# LEDFLX.net
KiCad netlist of a schematic drawn in Altium Designer
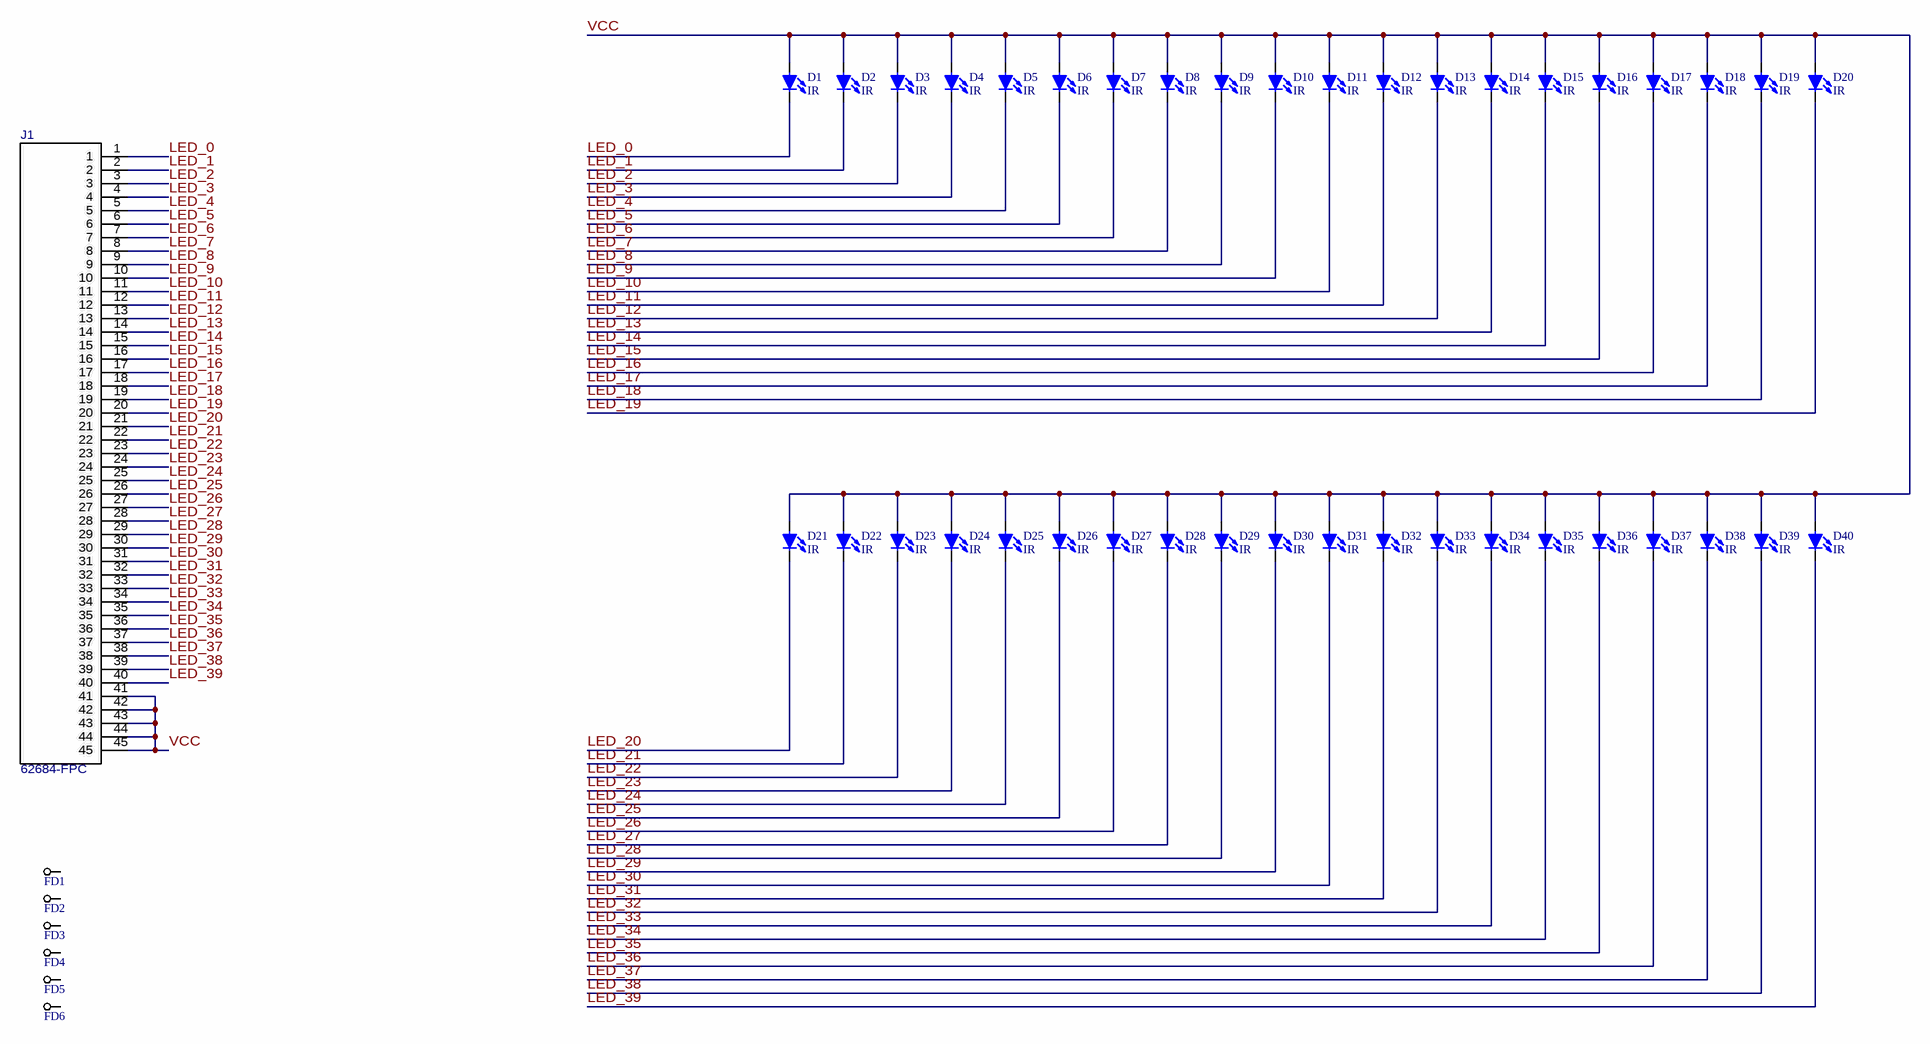
[diagram p0: LEDFLX.SchDoc]

(export (version "E")
  (design (tool "Eeschema 10.0.6"))
  (components
    (comp (ref "D1")
      (value "LED")
      (footprint "VISHAY_PLCC2_A")
      (fields (field (name "MANUFACTURER") "Vishay") (field (name "COLOR") "IR"))
      (libsource (lib "master") (part "LED"))
    )
    (comp (ref "D2")
      (value "LED")
      (footprint "VISHAY_PLCC2_A")
      (fields (field (name "MANUFACTURER") "Vishay") (field (name "COLOR") "IR"))
      (libsource (lib "master") (part "LED"))
    )
    (comp (ref "D3")
      (value "LED")
      (footprint "VISHAY_PLCC2_A")
      (fields (field (name "MANUFACTURER") "Vishay") (field (name "COLOR") "IR"))
      (libsource (lib "master") (part "LED"))
    )
    (comp (ref "D4")
      (value "LED")
      (footprint "VISHAY_PLCC2_A")
      (fields (field (name "MANUFACTURER") "Vishay") (field (name "COLOR") "IR"))
      (libsource (lib "master") (part "LED"))
    )
    (comp (ref "D5")
      (value "LED")
      (footprint "VISHAY_PLCC2_A")
      (fields (field (name "MANUFACTURER") "Vishay") (field (name "COLOR") "IR"))
      (libsource (lib "master") (part "LED"))
    )
    (comp (ref "D6")
      (value "LED")
      (footprint "VISHAY_PLCC2_A")
      (fields (field (name "MANUFACTURER") "Vishay") (field (name "COLOR") "IR"))
      (libsource (lib "master") (part "LED"))
    )
    (comp (ref "D7")
      (value "LED")
      (footprint "VISHAY_PLCC2_A")
      (fields (field (name "MANUFACTURER") "Vishay") (field (name "COLOR") "IR"))
      (libsource (lib "master") (part "LED"))
    )
    (comp (ref "D8")
      (value "LED")
      (footprint "VISHAY_PLCC2_A")
      (fields (field (name "MANUFACTURER") "Vishay") (field (name "COLOR") "IR"))
      (libsource (lib "master") (part "LED"))
    )
    (comp (ref "D9")
      (value "LED")
      (footprint "VISHAY_PLCC2_A")
      (fields (field (name "MANUFACTURER") "Vishay") (field (name "COLOR") "IR"))
      (libsource (lib "master") (part "LED"))
    )
    (comp (ref "D10")
      (value "LED")
      (footprint "VISHAY_PLCC2_A")
      (fields (field (name "MANUFACTURER") "Vishay") (field (name "COLOR") "IR"))
      (libsource (lib "master") (part "LED"))
    )
    (comp (ref "D11")
      (value "LED")
      (footprint "VISHAY_PLCC2_A")
      (fields (field (name "MANUFACTURER") "Vishay") (field (name "COLOR") "IR"))
      (libsource (lib "master") (part "LED"))
    )
    (comp (ref "D12")
      (value "LED")
      (footprint "VISHAY_PLCC2_A")
      (fields (field (name "MANUFACTURER") "Vishay") (field (name "COLOR") "IR"))
      (libsource (lib "master") (part "LED"))
    )
    (comp (ref "D13")
      (value "LED")
      (footprint "VISHAY_PLCC2_A")
      (fields (field (name "MANUFACTURER") "Vishay") (field (name "COLOR") "IR"))
      (libsource (lib "master") (part "LED"))
    )
    (comp (ref "D14")
      (value "LED")
      (footprint "VISHAY_PLCC2_A")
      (fields (field (name "MANUFACTURER") "Vishay") (field (name "COLOR") "IR"))
      (libsource (lib "master") (part "LED"))
    )
    (comp (ref "D15")
      (value "LED")
      (footprint "VISHAY_PLCC2_A")
      (fields (field (name "MANUFACTURER") "Vishay") (field (name "COLOR") "IR"))
      (libsource (lib "master") (part "LED"))
    )
    (comp (ref "D16")
      (value "LED")
      (footprint "VISHAY_PLCC2_A")
      (fields (field (name "MANUFACTURER") "Vishay") (field (name "COLOR") "IR"))
      (libsource (lib "master") (part "LED"))
    )
    (comp (ref "D17")
      (value "LED")
      (footprint "VISHAY_PLCC2_A")
      (fields (field (name "MANUFACTURER") "Vishay") (field (name "COLOR") "IR"))
      (libsource (lib "master") (part "LED"))
    )
    (comp (ref "D18")
      (value "LED")
      (footprint "VISHAY_PLCC2_A")
      (fields (field (name "MANUFACTURER") "Vishay") (field (name "COLOR") "IR"))
      (libsource (lib "master") (part "LED"))
    )
    (comp (ref "D19")
      (value "LED")
      (footprint "VISHAY_PLCC2_A")
      (fields (field (name "MANUFACTURER") "Vishay") (field (name "COLOR") "IR"))
      (libsource (lib "master") (part "LED"))
    )
    (comp (ref "D20")
      (value "LED")
      (footprint "VISHAY_PLCC2_A")
      (fields (field (name "MANUFACTURER") "Vishay") (field (name "COLOR") "IR"))
      (libsource (lib "master") (part "LED"))
    )
    (comp (ref "D21")
      (value "LED")
      (footprint "VISHAY_PLCC2_A")
      (fields (field (name "MANUFACTURER") "Vishay") (field (name "COLOR") "IR"))
      (libsource (lib "master") (part "LED"))
    )
    (comp (ref "D22")
      (value "LED")
      (footprint "VISHAY_PLCC2_A")
      (fields (field (name "MANUFACTURER") "Vishay") (field (name "COLOR") "IR"))
      (libsource (lib "master") (part "LED"))
    )
    (comp (ref "D23")
      (value "LED")
      (footprint "VISHAY_PLCC2_A")
      (fields (field (name "MANUFACTURER") "Vishay") (field (name "COLOR") "IR"))
      (libsource (lib "master") (part "LED"))
    )
    (comp (ref "D24")
      (value "LED")
      (footprint "VISHAY_PLCC2_A")
      (fields (field (name "MANUFACTURER") "Vishay") (field (name "COLOR") "IR"))
      (libsource (lib "master") (part "LED"))
    )
    (comp (ref "D25")
      (value "LED")
      (footprint "VISHAY_PLCC2_A")
      (fields (field (name "MANUFACTURER") "Vishay") (field (name "COLOR") "IR"))
      (libsource (lib "master") (part "LED"))
    )
    (comp (ref "D26")
      (value "LED")
      (footprint "VISHAY_PLCC2_A")
      (fields (field (name "MANUFACTURER") "Vishay") (field (name "COLOR") "IR"))
      (libsource (lib "master") (part "LED"))
    )
    (comp (ref "D27")
      (value "LED")
      (footprint "VISHAY_PLCC2_A")
      (fields (field (name "MANUFACTURER") "Vishay") (field (name "COLOR") "IR"))
      (libsource (lib "master") (part "LED"))
    )
    (comp (ref "D28")
      (value "LED")
      (footprint "VISHAY_PLCC2_A")
      (fields (field (name "MANUFACTURER") "Vishay") (field (name "COLOR") "IR"))
      (libsource (lib "master") (part "LED"))
    )
    (comp (ref "D29")
      (value "LED")
      (footprint "VISHAY_PLCC2_A")
      (fields (field (name "MANUFACTURER") "Vishay") (field (name "COLOR") "IR"))
      (libsource (lib "master") (part "LED"))
    )
    (comp (ref "D30")
      (value "LED")
      (footprint "VISHAY_PLCC2_A")
      (fields (field (name "MANUFACTURER") "Vishay") (field (name "COLOR") "IR"))
      (libsource (lib "master") (part "LED"))
    )
    (comp (ref "D31")
      (value "LED")
      (footprint "VISHAY_PLCC2_A")
      (fields (field (name "MANUFACTURER") "Vishay") (field (name "COLOR") "IR"))
      (libsource (lib "master") (part "LED"))
    )
    (comp (ref "D32")
      (value "LED")
      (footprint "VISHAY_PLCC2_A")
      (fields (field (name "MANUFACTURER") "Vishay") (field (name "COLOR") "IR"))
      (libsource (lib "master") (part "LED"))
    )
    (comp (ref "D33")
      (value "LED")
      (footprint "VISHAY_PLCC2_A")
      (fields (field (name "MANUFACTURER") "Vishay") (field (name "COLOR") "IR"))
      (libsource (lib "master") (part "LED"))
    )
    (comp (ref "D34")
      (value "LED")
      (footprint "VISHAY_PLCC2_A")
      (fields (field (name "MANUFACTURER") "Vishay") (field (name "COLOR") "IR"))
      (libsource (lib "master") (part "LED"))
    )
    (comp (ref "D35")
      (value "LED")
      (footprint "VISHAY_PLCC2_A")
      (fields (field (name "MANUFACTURER") "Vishay") (field (name "COLOR") "IR"))
      (libsource (lib "master") (part "LED"))
    )
    (comp (ref "D36")
      (value "LED")
      (footprint "VISHAY_PLCC2_A")
      (fields (field (name "MANUFACTURER") "Vishay") (field (name "COLOR") "IR"))
      (libsource (lib "master") (part "LED"))
    )
    (comp (ref "D37")
      (value "LED")
      (footprint "VISHAY_PLCC2_A")
      (fields (field (name "MANUFACTURER") "Vishay") (field (name "COLOR") "IR"))
      (libsource (lib "master") (part "LED"))
    )
    (comp (ref "D38")
      (value "LED")
      (footprint "VISHAY_PLCC2_A")
      (fields (field (name "MANUFACTURER") "Vishay") (field (name "COLOR") "IR"))
      (libsource (lib "master") (part "LED"))
    )
    (comp (ref "D39")
      (value "LED")
      (footprint "VISHAY_PLCC2_A")
      (fields (field (name "MANUFACTURER") "Vishay") (field (name "COLOR") "IR"))
      (libsource (lib "master") (part "LED"))
    )
    (comp (ref "D40")
      (value "LED")
      (footprint "VISHAY_PLCC2_A")
      (fields (field (name "MANUFACTURER") "Vishay") (field (name "COLOR") "IR"))
      (libsource (lib "master") (part "LED"))
    )
    (comp (ref "FD1") (value "FIDUCIAL") (footprint "FIDUCIAL") (libsource (lib "master") (part "FIDUCIAL")))
    (comp (ref "FD2") (value "FIDUCIAL") (footprint "FIDUCIAL") (libsource (lib "master") (part "FIDUCIAL")))
    (comp (ref "FD3") (value "FIDUCIAL") (footprint "FIDUCIAL") (libsource (lib "master") (part "FIDUCIAL")))
    (comp (ref "FD4") (value "FIDUCIAL") (footprint "FIDUCIAL") (libsource (lib "master") (part "FIDUCIAL")))
    (comp (ref "FD5") (value "FIDUCIAL") (footprint "FIDUCIAL") (libsource (lib "master") (part "FIDUCIAL")))
    (comp (ref "FD6") (value "FIDUCIAL") (footprint "FIDUCIAL") (libsource (lib "master") (part "FIDUCIAL")))
    (comp (ref "J1")
      (value "62684-FPC")
      (footprint "FCI_62684-FLEX_SIDE")
      (fields (field (name "MANUFACTURER") "FCI"))
      (libsource (lib "master") (part "FCI_62684-FLEX"))
    )
  )
  (nets
    (net (code "1") (name "/LED_0") (class "Default")
      (node (ref "D1") (pin "2") (pinfunction "C_2") (pintype "passive"))
      (node (ref "J1") (pin "1") (pinfunction "1_1") (pintype "passive"))
    )
    (net (code "2") (name "/LED_1") (class "Default")
      (node (ref "D2") (pin "2") (pinfunction "C_2") (pintype "passive"))
      (node (ref "J1") (pin "2") (pinfunction "2_2") (pintype "passive"))
    )
    (net (code "3") (name "/LED_2") (class "Default")
      (node (ref "D3") (pin "2") (pinfunction "C_2") (pintype "passive"))
      (node (ref "J1") (pin "3") (pinfunction "3_3") (pintype "passive"))
    )
    (net (code "4") (name "/LED_3") (class "Default")
      (node (ref "D4") (pin "2") (pinfunction "C_2") (pintype "passive"))
      (node (ref "J1") (pin "4") (pinfunction "4_4") (pintype "passive"))
    )
    (net (code "5") (name "/LED_4") (class "Default")
      (node (ref "D5") (pin "2") (pinfunction "C_2") (pintype "passive"))
      (node (ref "J1") (pin "5") (pinfunction "5_5") (pintype "passive"))
    )
    (net (code "6") (name "/LED_5") (class "Default")
      (node (ref "D6") (pin "2") (pinfunction "C_2") (pintype "passive"))
      (node (ref "J1") (pin "6") (pinfunction "6_6") (pintype "passive"))
    )
    (net (code "7") (name "/LED_6") (class "Default")
      (node (ref "D7") (pin "2") (pinfunction "C_2") (pintype "passive"))
      (node (ref "J1") (pin "7") (pinfunction "7_7") (pintype "passive"))
    )
    (net (code "8") (name "/LED_7") (class "Default")
      (node (ref "D8") (pin "2") (pinfunction "C_2") (pintype "passive"))
      (node (ref "J1") (pin "8") (pinfunction "8_8") (pintype "passive"))
    )
    (net (code "9") (name "/LED_8") (class "Default")
      (node (ref "D9") (pin "2") (pinfunction "C_2") (pintype "passive"))
      (node (ref "J1") (pin "9") (pinfunction "9_9") (pintype "passive"))
    )
    (net (code "10") (name "/LED_9") (class "Default")
      (node (ref "D10") (pin "2") (pinfunction "C_2") (pintype "passive"))
      (node (ref "J1") (pin "10") (pinfunction "10_10") (pintype "passive"))
    )
    (net (code "11") (name "/LED_10") (class "Default")
      (node (ref "D11") (pin "2") (pinfunction "C_2") (pintype "passive"))
      (node (ref "J1") (pin "11") (pinfunction "11_11") (pintype "passive"))
    )
    (net (code "12") (name "/LED_11") (class "Default")
      (node (ref "D12") (pin "2") (pinfunction "C_2") (pintype "passive"))
      (node (ref "J1") (pin "12") (pinfunction "12_12") (pintype "passive"))
    )
    (net (code "13") (name "/LED_12") (class "Default")
      (node (ref "D13") (pin "2") (pinfunction "C_2") (pintype "passive"))
      (node (ref "J1") (pin "13") (pinfunction "13_13") (pintype "passive"))
    )
    (net (code "14") (name "/LED_13") (class "Default")
      (node (ref "D14") (pin "2") (pinfunction "C_2") (pintype "passive"))
      (node (ref "J1") (pin "14") (pinfunction "14_14") (pintype "passive"))
    )
    (net (code "15") (name "/LED_14") (class "Default")
      (node (ref "D15") (pin "2") (pinfunction "C_2") (pintype "passive"))
      (node (ref "J1") (pin "15") (pinfunction "15_15") (pintype "passive"))
    )
    (net (code "16") (name "/LED_15") (class "Default")
      (node (ref "D16") (pin "2") (pinfunction "C_2") (pintype "passive"))
      (node (ref "J1") (pin "16") (pinfunction "16_16") (pintype "passive"))
    )
    (net (code "17") (name "/LED_16") (class "Default")
      (node (ref "D17") (pin "2") (pinfunction "C_2") (pintype "passive"))
      (node (ref "J1") (pin "17") (pinfunction "17_17") (pintype "passive"))
    )
    (net (code "18") (name "/LED_17") (class "Default")
      (node (ref "D18") (pin "2") (pinfunction "C_2") (pintype "passive"))
      (node (ref "J1") (pin "18") (pinfunction "18_18") (pintype "passive"))
    )
    (net (code "19") (name "/LED_18") (class "Default")
      (node (ref "D19") (pin "2") (pinfunction "C_2") (pintype "passive"))
      (node (ref "J1") (pin "19") (pinfunction "19_19") (pintype "passive"))
    )
    (net (code "20") (name "/LED_19") (class "Default")
      (node (ref "D20") (pin "2") (pinfunction "C_2") (pintype "passive"))
      (node (ref "J1") (pin "20") (pinfunction "20_20") (pintype "passive"))
    )
    (net (code "21") (name "/LED_20") (class "Default")
      (node (ref "D21") (pin "2") (pinfunction "C_2") (pintype "passive"))
      (node (ref "J1") (pin "21") (pinfunction "21_21") (pintype "passive"))
    )
    (net (code "22") (name "/LED_21") (class "Default")
      (node (ref "D22") (pin "2") (pinfunction "C_2") (pintype "passive"))
      (node (ref "J1") (pin "22") (pinfunction "22_22") (pintype "passive"))
    )
    (net (code "23") (name "/LED_22") (class "Default")
      (node (ref "D23") (pin "2") (pinfunction "C_2") (pintype "passive"))
      (node (ref "J1") (pin "23") (pinfunction "23_23") (pintype "passive"))
    )
    (net (code "24") (name "/LED_23") (class "Default")
      (node (ref "D24") (pin "2") (pinfunction "C_2") (pintype "passive"))
      (node (ref "J1") (pin "24") (pinfunction "24_24") (pintype "passive"))
    )
    (net (code "25") (name "/LED_24") (class "Default")
      (node (ref "D25") (pin "2") (pinfunction "C_2") (pintype "passive"))
      (node (ref "J1") (pin "25") (pinfunction "25_25") (pintype "passive"))
    )
    (net (code "26") (name "/LED_25") (class "Default")
      (node (ref "D26") (pin "2") (pinfunction "C_2") (pintype "passive"))
      (node (ref "J1") (pin "26") (pinfunction "26_26") (pintype "passive"))
    )
    (net (code "27") (name "/LED_26") (class "Default")
      (node (ref "D27") (pin "2") (pinfunction "C_2") (pintype "passive"))
      (node (ref "J1") (pin "27") (pinfunction "27_27") (pintype "passive"))
    )
    (net (code "28") (name "/LED_27") (class "Default")
      (node (ref "D28") (pin "2") (pinfunction "C_2") (pintype "passive"))
      (node (ref "J1") (pin "28") (pinfunction "28_28") (pintype "passive"))
    )
    (net (code "29") (name "/LED_28") (class "Default")
      (node (ref "D29") (pin "2") (pinfunction "C_2") (pintype "passive"))
      (node (ref "J1") (pin "29") (pinfunction "29_29") (pintype "passive"))
    )
    (net (code "30") (name "/LED_29") (class "Default")
      (node (ref "D30") (pin "2") (pinfunction "C_2") (pintype "passive"))
      (node (ref "J1") (pin "30") (pinfunction "30_30") (pintype "passive"))
    )
    (net (code "31") (name "/LED_30") (class "Default")
      (node (ref "D31") (pin "2") (pinfunction "C_2") (pintype "passive"))
      (node (ref "J1") (pin "31") (pinfunction "31_31") (pintype "passive"))
    )
    (net (code "32") (name "/LED_31") (class "Default")
      (node (ref "D32") (pin "2") (pinfunction "C_2") (pintype "passive"))
      (node (ref "J1") (pin "32") (pinfunction "32_32") (pintype "passive"))
    )
    (net (code "33") (name "/LED_32") (class "Default")
      (node (ref "D33") (pin "2") (pinfunction "C_2") (pintype "passive"))
      (node (ref "J1") (pin "33") (pinfunction "33_33") (pintype "passive"))
    )
    (net (code "34") (name "/LED_33") (class "Default")
      (node (ref "D34") (pin "2") (pinfunction "C_2") (pintype "passive"))
      (node (ref "J1") (pin "34") (pinfunction "34_34") (pintype "passive"))
    )
    (net (code "35") (name "/LED_34") (class "Default")
      (node (ref "D35") (pin "2") (pinfunction "C_2") (pintype "passive"))
      (node (ref "J1") (pin "35") (pinfunction "35_35") (pintype "passive"))
    )
    (net (code "36") (name "/LED_35") (class "Default")
      (node (ref "D36") (pin "2") (pinfunction "C_2") (pintype "passive"))
      (node (ref "J1") (pin "36") (pinfunction "36_36") (pintype "passive"))
    )
    (net (code "37") (name "/LED_36") (class "Default")
      (node (ref "D37") (pin "2") (pinfunction "C_2") (pintype "passive"))
      (node (ref "J1") (pin "37") (pinfunction "37_37") (pintype "passive"))
    )
    (net (code "38") (name "/LED_37") (class "Default")
      (node (ref "D38") (pin "2") (pinfunction "C_2") (pintype "passive"))
      (node (ref "J1") (pin "38") (pinfunction "38_38") (pintype "passive"))
    )
    (net (code "39") (name "/LED_38") (class "Default")
      (node (ref "D39") (pin "2") (pinfunction "C_2") (pintype "passive"))
      (node (ref "J1") (pin "39") (pinfunction "39_39") (pintype "passive"))
    )
    (net (code "40") (name "/LED_39") (class "Default")
      (node (ref "D40") (pin "2") (pinfunction "C_2") (pintype "passive"))
      (node (ref "J1") (pin "40") (pinfunction "40_40") (pintype "passive"))
    )
    (net (code "41") (name "/VCC") (class "Default")
      (node (ref "D1") (pin "1") (pinfunction "A_1") (pintype "passive"))
      (node (ref "D10") (pin "1") (pinfunction "A_1") (pintype "passive"))
      (node (ref "D11") (pin "1") (pinfunction "A_1") (pintype "passive"))
      (node (ref "D12") (pin "1") (pinfunction "A_1") (pintype "passive"))
      (node (ref "D13") (pin "1") (pinfunction "A_1") (pintype "passive"))
      (node (ref "D14") (pin "1") (pinfunction "A_1") (pintype "passive"))
      (node (ref "D15") (pin "1") (pinfunction "A_1") (pintype "passive"))
      (node (ref "D16") (pin "1") (pinfunction "A_1") (pintype "passive"))
      (node (ref "D17") (pin "1") (pinfunction "A_1") (pintype "passive"))
      (node (ref "D18") (pin "1") (pinfunction "A_1") (pintype "passive"))
      (node (ref "D19") (pin "1") (pinfunction "A_1") (pintype "passive"))
      (node (ref "D2") (pin "1") (pinfunction "A_1") (pintype "passive"))
      (node (ref "D20") (pin "1") (pinfunction "A_1") (pintype "passive"))
      (node (ref "D21") (pin "1") (pinfunction "A_1") (pintype "passive"))
      (node (ref "D22") (pin "1") (pinfunction "A_1") (pintype "passive"))
      (node (ref "D23") (pin "1") (pinfunction "A_1") (pintype "passive"))
      (node (ref "D24") (pin "1") (pinfunction "A_1") (pintype "passive"))
      (node (ref "D25") (pin "1") (pinfunction "A_1") (pintype "passive"))
      (node (ref "D26") (pin "1") (pinfunction "A_1") (pintype "passive"))
      (node (ref "D27") (pin "1") (pinfunction "A_1") (pintype "passive"))
      (node (ref "D28") (pin "1") (pinfunction "A_1") (pintype "passive"))
      (node (ref "D29") (pin "1") (pinfunction "A_1") (pintype "passive"))
      (node (ref "D3") (pin "1") (pinfunction "A_1") (pintype "passive"))
      (node (ref "D30") (pin "1") (pinfunction "A_1") (pintype "passive"))
      (node (ref "D31") (pin "1") (pinfunction "A_1") (pintype "passive"))
      (node (ref "D32") (pin "1") (pinfunction "A_1") (pintype "passive"))
      (node (ref "D33") (pin "1") (pinfunction "A_1") (pintype "passive"))
      (node (ref "D34") (pin "1") (pinfunction "A_1") (pintype "passive"))
      (node (ref "D35") (pin "1") (pinfunction "A_1") (pintype "passive"))
      (node (ref "D36") (pin "1") (pinfunction "A_1") (pintype "passive"))
      (node (ref "D37") (pin "1") (pinfunction "A_1") (pintype "passive"))
      (node (ref "D38") (pin "1") (pinfunction "A_1") (pintype "passive"))
      (node (ref "D39") (pin "1") (pinfunction "A_1") (pintype "passive"))
      (node (ref "D4") (pin "1") (pinfunction "A_1") (pintype "passive"))
      (node (ref "D40") (pin "1") (pinfunction "A_1") (pintype "passive"))
      (node (ref "D5") (pin "1") (pinfunction "A_1") (pintype "passive"))
      (node (ref "D6") (pin "1") (pinfunction "A_1") (pintype "passive"))
      (node (ref "D7") (pin "1") (pinfunction "A_1") (pintype "passive"))
      (node (ref "D8") (pin "1") (pinfunction "A_1") (pintype "passive"))
      (node (ref "D9") (pin "1") (pinfunction "A_1") (pintype "passive"))
      (node (ref "J1") (pin "41") (pinfunction "41_41") (pintype "passive"))
      (node (ref "J1") (pin "42") (pinfunction "42_42") (pintype "passive"))
      (node (ref "J1") (pin "43") (pinfunction "43_43") (pintype "passive"))
      (node (ref "J1") (pin "44") (pinfunction "44_44") (pintype "passive"))
      (node (ref "J1") (pin "45") (pinfunction "45_45") (pintype "passive"))
    )
    (net (code "42") (name "unconnected-(FD1-Pad1)") (class "Default")
      (node (ref "FD1") (pin "1") (pinfunction "1_1") (pintype "passive"))
    )
    (net (code "43") (name "unconnected-(FD2-Pad1)") (class "Default")
      (node (ref "FD2") (pin "1") (pinfunction "1_1") (pintype "passive"))
    )
    (net (code "44") (name "unconnected-(FD3-Pad1)") (class "Default")
      (node (ref "FD3") (pin "1") (pinfunction "1_1") (pintype "passive"))
    )
    (net (code "45") (name "unconnected-(FD4-Pad1)") (class "Default")
      (node (ref "FD4") (pin "1") (pinfunction "1_1") (pintype "passive"))
    )
    (net (code "46") (name "unconnected-(FD5-Pad1)") (class "Default")
      (node (ref "FD5") (pin "1") (pinfunction "1_1") (pintype "passive"))
    )
    (net (code "47") (name "unconnected-(FD6-Pad1)") (class "Default")
      (node (ref "FD6") (pin "1") (pinfunction "1_1") (pintype "passive"))
    )
  )
)
